# Matching_Network_V1p1.net
KiCad netlist of a schematic drawn in EAGLE
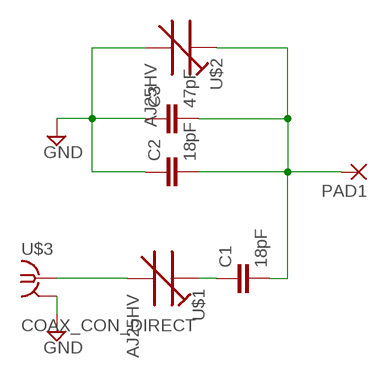
[diagram p0: schematic, sheet 1]

(export (version "E")
  (design (tool "Eeschema 10.0.6"))
  (components
    (comp (ref "C1")
      (value "18pF")
      (footprint "eagle-import:C1210")
      (libsource (lib "eagle-import") (part "C-EUC1210"))
    )
    (comp (ref "C2")
      (value "18pF")
      (footprint "eagle-import:C1210")
      (libsource (lib "eagle-import") (part "C-EUC1210"))
    )
    (comp (ref "C3")
      (value "47pF")
      (footprint "eagle-import:C1210")
      (libsource (lib "eagle-import") (part "C-EUC1210"))
    )
    (comp (ref "PAD1")
      (value "SMD5")
      (footprint "eagle-import:SMD2,54-5,08")
      (libsource (lib "eagle-import") (part "SMD5"))
    )
    (comp (ref "U$1")
      (value "AJ25HV")
      (footprint "eagle-import:AJ25HV")
      (libsource (lib "eagle-import") (part "AJ25HV"))
    )
    (comp (ref "U$2")
      (value "AJ25HV")
      (footprint "eagle-import:AJ25HV")
      (libsource (lib "eagle-import") (part "AJ25HV"))
    )
    (comp (ref "U$3")
      (value "COAX_CON_DIRECT")
      (footprint "eagle-import:COAX.141")
      (libsource (lib "eagle-import") (part "COAX_CON_DIRECT"))
    )
  )
  (nets
    (net (code "1") (name "GND") (class "Default")
      (node (ref "C2") (pin "1") (pinfunction "1_1") (pintype "passive"))
      (node (ref "C3") (pin "1") (pinfunction "1_1") (pintype "passive"))
      (node (ref "U$2") (pin "P$1") (pinfunction "A_P$1") (pintype "passive"))
      (node (ref "U$3") (pin "P$2") (pinfunction "GND_P$2") (pintype "passive"))
    )
    (net (code "2") (name "Net-(PAD1-P)") (class "Default")
      (node (ref "C1") (pin "2") (pinfunction "2_2") (pintype "passive"))
      (node (ref "C2") (pin "2") (pinfunction "2_2") (pintype "passive"))
      (node (ref "C3") (pin "2") (pinfunction "2_2") (pintype "passive"))
      (node (ref "PAD1") (pin "1") (pinfunction "P_1") (pintype "passive"))
      (node (ref "U$2") (pin "P$2") (pinfunction "E_P$2") (pintype "passive"))
    )
    (net (code "3") (name "Net-(U$1-A)") (class "Default")
      (node (ref "U$1") (pin "P$1") (pinfunction "A_P$1") (pintype "passive"))
      (node (ref "U$3") (pin "P$1") (pinfunction "1_P$1") (pintype "passive"))
    )
    (net (code "4") (name "Net-(U$1-E)") (class "Default")
      (node (ref "C1") (pin "1") (pinfunction "1_1") (pintype "passive"))
      (node (ref "U$1") (pin "P$2") (pinfunction "E_P$2") (pintype "passive"))
    )
  )
)
